# D5035-51.net
KiCad netlist of a schematic drawn in Altium Designer
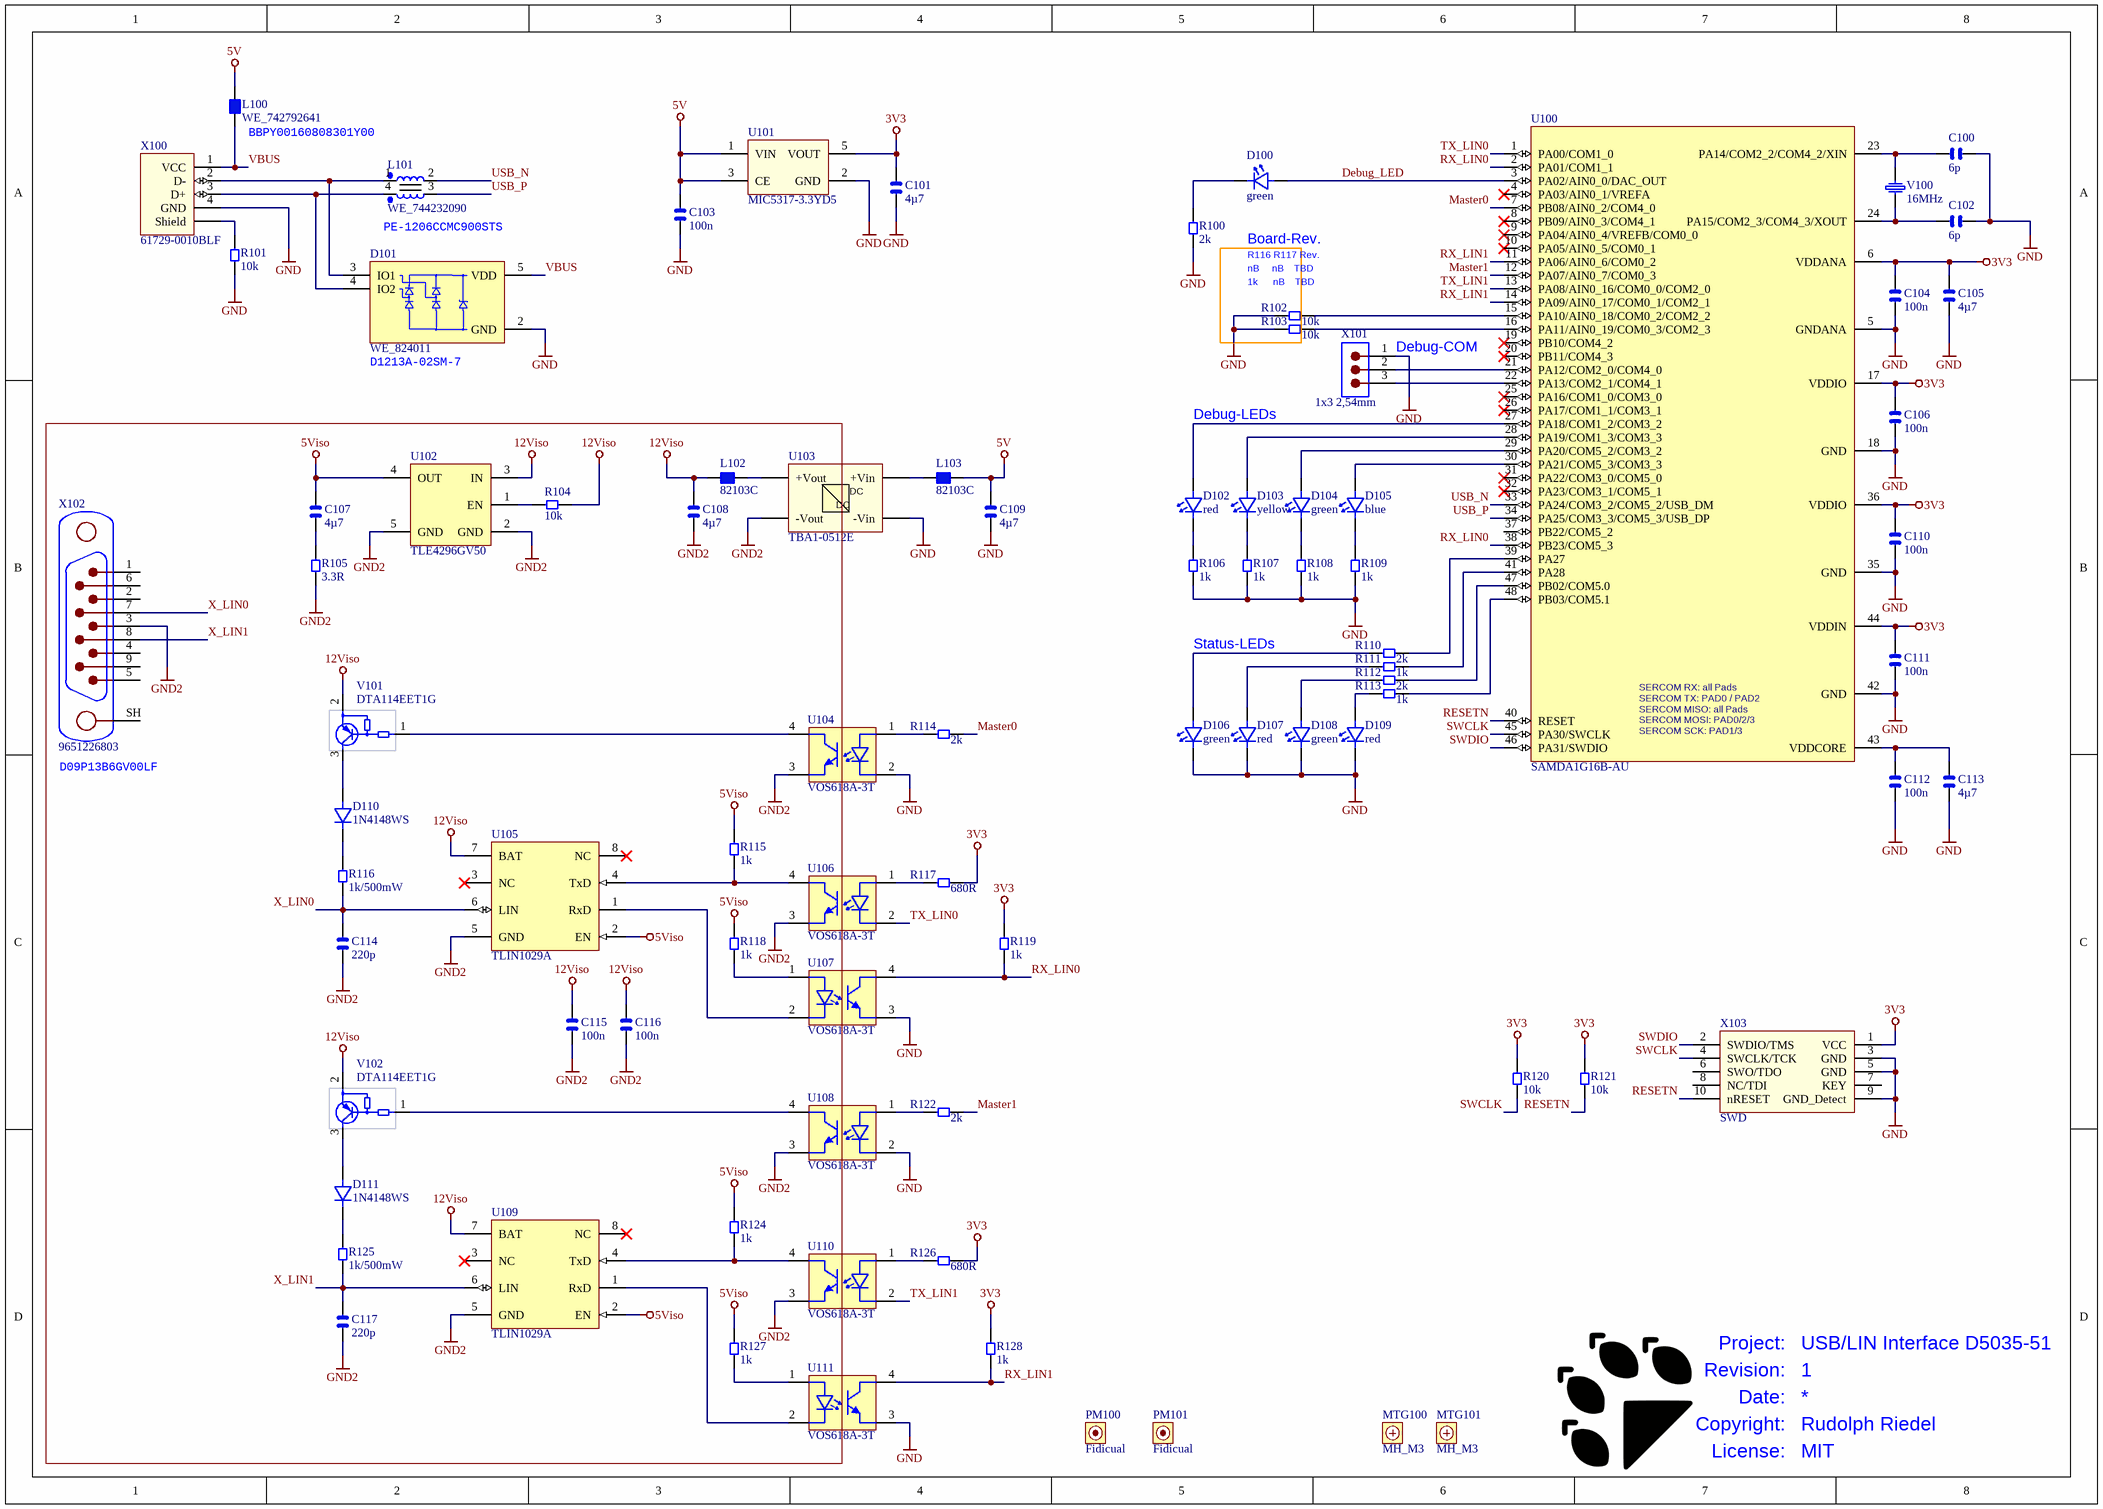
[diagram p0: D5035-51.SchDoc]

(export (version "E")
  (design (tool "Eeschema 10.0.6"))
  (components
    (comp (ref "C100")
      (value "6p")
      (footprint "CAPC1608X09L")
      (description "0603 Chip Capacitor")
      (fields (field (name "PART NUMBER") "CAPC_0603") (field (name "EDITOR") "rriedel"))
      (libsource (lib "HW-Labor_GF") (part "CAP_2_V2"))
    )
    (comp (ref "C101")
      (value "4µ7")
      (footprint "CAPC2012X14L")
      (description "0805 Chip Capacitor")
      (fields (field (name "PART NUMBER") "CAPC_0805") (field (name "EDITOR") "rriedel"))
      (libsource (lib "HW-Labor_GF") (part "CAP_2_V2"))
    )
    (comp (ref "C102")
      (value "6p")
      (footprint "CAPC1608X09L")
      (description "0603 Chip Capacitor")
      (fields (field (name "PART NUMBER") "CAPC_0603") (field (name "EDITOR") "rriedel"))
      (libsource (lib "HW-Labor_GF") (part "CAP_2_V2"))
    )
    (comp (ref "C103")
      (value "100n")
      (footprint "CAPC1608X09L")
      (description "0603 Chip Capacitor")
      (fields (field (name "PART NUMBER") "CAPC_0603") (field (name "EDITOR") "rriedel"))
      (libsource (lib "HW-Labor_GF") (part "CAP_2_V2"))
    )
    (comp (ref "C104")
      (value "100n")
      (footprint "CAPC1608X09L")
      (description "0603 Chip Capacitor")
      (fields (field (name "PART NUMBER") "CAPC_0603") (field (name "EDITOR") "rriedel"))
      (libsource (lib "HW-Labor_GF") (part "CAP_2_V2"))
    )
    (comp (ref "C105")
      (value "4µ7")
      (footprint "CAPC2012X14L")
      (description "0805 Chip Capacitor")
      (fields (field (name "PART NUMBER") "CAPC_0805") (field (name "EDITOR") "rriedel"))
      (libsource (lib "HW-Labor_GF") (part "CAP_2_V2"))
    )
    (comp (ref "C106")
      (value "100n")
      (footprint "CAPC1608X09L")
      (description "0603 Chip Capacitor")
      (fields (field (name "PART NUMBER") "CAPC_0603") (field (name "EDITOR") "rriedel"))
      (libsource (lib "HW-Labor_GF") (part "CAP_2_V2"))
    )
    (comp (ref "C107")
      (value "4µ7")
      (footprint "CAPC2012X14L")
      (description "0805 Chip Capacitor")
      (fields (field (name "PART NUMBER") "CAPC_0805") (field (name "EDITOR") "rriedel"))
      (libsource (lib "HW-Labor_GF") (part "CAP_2_V2"))
    )
    (comp (ref "C108")
      (value "4µ7")
      (footprint "CAPC2012X14L")
      (description "0805 Chip Capacitor")
      (fields (field (name "PART NUMBER") "CAPC_0805") (field (name "EDITOR") "rriedel"))
      (libsource (lib "HW-Labor_GF") (part "CAP_2_V2"))
    )
    (comp (ref "C109")
      (value "4µ7")
      (footprint "CAPC2012X14L")
      (description "0805 Chip Capacitor")
      (fields (field (name "PART NUMBER") "CAPC_0805") (field (name "EDITOR") "rriedel"))
      (libsource (lib "HW-Labor_GF") (part "CAP_2_V2"))
    )
    (comp (ref "C110")
      (value "100n")
      (footprint "CAPC1608X09L")
      (description "0603 Chip Capacitor")
      (fields (field (name "PART NUMBER") "CAPC_0603") (field (name "EDITOR") "rriedel"))
      (libsource (lib "HW-Labor_GF") (part "CAP_2_V2"))
    )
    (comp (ref "C111")
      (value "100n")
      (footprint "CAPC1608X09L")
      (description "0603 Chip Capacitor")
      (fields (field (name "PART NUMBER") "CAPC_0603") (field (name "EDITOR") "rriedel"))
      (libsource (lib "HW-Labor_GF") (part "CAP_2_V2"))
    )
    (comp (ref "C112")
      (value "100n")
      (footprint "CAPC1608X09L")
      (description "0603 Chip Capacitor")
      (fields (field (name "PART NUMBER") "CAPC_0603") (field (name "EDITOR") "rriedel"))
      (libsource (lib "HW-Labor_GF") (part "CAP_2_V2"))
    )
    (comp (ref "C113")
      (value "4µ7")
      (footprint "CAPC2012X14L")
      (description "0805 Chip Capacitor")
      (fields (field (name "PART NUMBER") "CAPC_0805") (field (name "EDITOR") "rriedel"))
      (libsource (lib "HW-Labor_GF") (part "CAP_2_V2"))
    )
    (comp (ref "C114")
      (value "220p")
      (footprint "CAPC2012X14L")
      (description "0805 Chip Capacitor")
      (fields (field (name "PART NUMBER") "CAPC_0805") (field (name "EDITOR") "rriedel"))
      (libsource (lib "HW-Labor_GF") (part "CAP_2_V2"))
    )
    (comp (ref "C115")
      (value "100n")
      (footprint "CAPC1608X09L")
      (description "0603 Chip Capacitor")
      (fields (field (name "PART NUMBER") "CAPC_0603") (field (name "EDITOR") "rriedel"))
      (libsource (lib "HW-Labor_GF") (part "CAP_2_V2"))
    )
    (comp (ref "C116")
      (value "100n")
      (footprint "CAPC1608X09L")
      (description "0603 Chip Capacitor")
      (fields (field (name "PART NUMBER") "CAPC_0603") (field (name "EDITOR") "rriedel"))
      (libsource (lib "HW-Labor_GF") (part "CAP_2_V2"))
    )
    (comp (ref "C117")
      (value "220p")
      (footprint "CAPC2012X14L")
      (description "0805 Chip Capacitor")
      (fields (field (name "PART NUMBER") "CAPC_0805") (field (name "EDITOR") "rriedel"))
      (libsource (lib "HW-Labor_GF") (part "CAP_2_V2"))
    )
    (comp (ref "D100")
      (value "green")
      (footprint "DIOC1608X06N_LED")
      (description "LED, 0603")
      (fields (field (name "PART NUMBER") "LED_0603") (field (name "EDITOR") "rriedel"))
      (libsource (lib "HW-Labor_GF") (part "LED_generic"))
    )
    (comp (ref "D101")
      (value "WE_824011")
      (footprint "SOT95P280X110-5N")
      (description "TVS Diode Array WE-TVS")
      (fields
        (field (name "MANUFACTURER") "Wuerth")
        (field (name "DISTRIBUTOR_1_PART_NUMBER") "732-4465-1-ND")
        (field (name "EDITOR") "rriedel")
      )
      (libsource (lib "HW-Labor_GF") (part "WE-824011"))
    )
    (comp (ref "D102")
      (value "red")
      (footprint "DIOC1608X06N_LED")
      (description "LED, 0603")
      (fields (field (name "PART NUMBER") "LED_0603") (field (name "EDITOR") "rriedel"))
      (libsource (lib "HW-Labor_GF") (part "LED_generic"))
    )
    (comp (ref "D103")
      (value "yellow")
      (footprint "DIOC1608X06N_LED")
      (description "LED, 0603")
      (fields (field (name "PART NUMBER") "LED_0603") (field (name "EDITOR") "rriedel"))
      (libsource (lib "HW-Labor_GF") (part "LED_generic"))
    )
    (comp (ref "D104")
      (value "green")
      (footprint "DIOC1608X06N_LED")
      (description "LED, 0603")
      (fields (field (name "PART NUMBER") "LED_0603") (field (name "EDITOR") "rriedel"))
      (libsource (lib "HW-Labor_GF") (part "LED_generic"))
    )
    (comp (ref "D105")
      (value "blue")
      (footprint "DIOC1608X06N_LED")
      (description "LED, 0603")
      (fields (field (name "PART NUMBER") "LED_0603") (field (name "EDITOR") "rriedel"))
      (libsource (lib "HW-Labor_GF") (part "LED_generic"))
    )
    (comp (ref "D106")
      (value "green")
      (footprint "DIOC1608X06N_LED")
      (description "LED, 0603")
      (fields (field (name "PART NUMBER") "LED_0603") (field (name "EDITOR") "rriedel"))
      (libsource (lib "HW-Labor_GF") (part "LED_generic"))
    )
    (comp (ref "D107")
      (value "red")
      (footprint "DIOC1608X06N_LED")
      (description "LED, 0603")
      (fields (field (name "PART NUMBER") "LED_0603") (field (name "EDITOR") "rriedel"))
      (libsource (lib "HW-Labor_GF") (part "LED_generic"))
    )
    (comp (ref "D108")
      (value "green")
      (footprint "DIOC1608X06N_LED")
      (description "LED, 0603")
      (fields (field (name "PART NUMBER") "LED_0603") (field (name "EDITOR") "rriedel"))
      (libsource (lib "HW-Labor_GF") (part "LED_generic"))
    )
    (comp (ref "D109")
      (value "red")
      (footprint "DIOC1608X06N_LED")
      (description "LED, 0603")
      (fields (field (name "PART NUMBER") "LED_0603") (field (name "EDITOR") "rriedel"))
      (libsource (lib "HW-Labor_GF") (part "LED_generic"))
    )
    (comp (ref "D110")
      (value "1N4148WS")
      (footprint "SOD323")
      (description "Small Signal Diode IF 0.15A, VR 75V, SOD323F")
      (fields (field (name "DISTRIBUTOR_1_PART_NUMBER") "C2128") (field (name "EDITOR") "rriedel"))
      (libsource (lib "HW-Labor_GF") (part "Diode_A2_K1"))
    )
    (comp (ref "D111")
      (value "1N4148WS")
      (footprint "SOD323")
      (description "Small Signal Diode IF 0.15A, VR 75V, SOD323F")
      (fields (field (name "DISTRIBUTOR_1_PART_NUMBER") "C2128") (field (name "EDITOR") "rriedel"))
      (libsource (lib "HW-Labor_GF") (part "Diode_A2_K1"))
    )
    (comp (ref "L100")
      (value "WE_742792641")
      (footprint "INDC1608X06L")
      (description "SMT EMI suppression ferrite bead WE-CBF")
      (fields
        (field (name "MANUFACTURER") "Wuerth")
        (field (name "DISTRIBUTOR_1_PART_NUMBER") "732-1592-1-ND")
        (field (name "EDITOR") "rriedel")
      )
      (libsource (lib "HW-Labor_GF") (part "IND_2_V1"))
    )
    (comp (ref "L101")
      (value "WE_744232090")
      (footprint "WE_744232090")
      (description "SMD common mode noise suppressor WE-CNSW")
      (fields
        (field (name "MANUFACTURER") "Wuerth")
        (field (name "DISTRIBUTOR_1_PART_NUMBER") "732-1469-1-ND")
        (field (name "EDITOR") "rriedel")
      )
      (libsource (lib "HW-Labor_GF") (part "WE_744232090"))
    )
    (comp (ref "L102")
      (value "82103C")
      (footprint "Murata_8200C")
      (description "10µH, 0,5A, 400mR")
      (fields
        (field (name "MANUFACTURER") "Murata")
        (field (name "DISTRIBUTOR_1_PART_NUMBER") "811-2473-1-ND")
        (field (name "EDITOR") "rriedel")
      )
      (libsource (lib "HW-Labor_GF") (part "IND_2_V1"))
    )
    (comp (ref "L103")
      (value "82103C")
      (footprint "Murata_8200C")
      (description "10µH, 0,5A, 400mR")
      (fields
        (field (name "MANUFACTURER") "Murata")
        (field (name "DISTRIBUTOR_1_PART_NUMBER") "811-2473-1-ND")
        (field (name "EDITOR") "rriedel")
      )
      (libsource (lib "HW-Labor_GF") (part "IND_2_V1"))
    )
    (comp (ref "MTG100")
      (value "MH_M3")
      (footprint "HOLE_3_2MM")
      (description "Mounting-Hole for M3 screws")
      (fields (field (name "EDITOR") "rriedel"))
      (libsource (lib "HW-Labor_GF") (part "MTG_V1"))
    )
    (comp (ref "MTG101")
      (value "MH_M3")
      (footprint "HOLE_3_2MM")
      (description "Mounting-Hole for M3 screws")
      (fields (field (name "EDITOR") "rriedel"))
      (libsource (lib "HW-Labor_GF") (part "MTG_V1"))
    )
    (comp (ref "PM100")
      (value "Fidicual")
      (footprint "PM100")
      (fields (field (name "PART NUMBER") "PM100") (field (name "EDITOR") "rriedel"))
      (libsource (lib "HW-Labor_GF") (part "PM100"))
    )
    (comp (ref "PM101")
      (value "Fidicual")
      (footprint "PM100")
      (fields (field (name "PART NUMBER") "PM100") (field (name "EDITOR") "rriedel"))
      (libsource (lib "HW-Labor_GF") (part "PM100"))
    )
    (comp (ref "R100")
      (value "2k")
      (footprint "RESC1608X06L")
      (description "0603 Chip Resistor")
      (fields (field (name "PART NUMBER") "RESC_0603") (field (name "EDITOR") "rriedel"))
      (libsource (lib "HW-Labor_GF") (part "RES_2_V2"))
    )
    (comp (ref "R101")
      (value "10k")
      (footprint "RESC1608X06L")
      (description "0603 Chip Resistor")
      (fields (field (name "PART NUMBER") "RESC_0603") (field (name "EDITOR") "rriedel"))
      (libsource (lib "HW-Labor_GF") (part "RES_2_V2"))
    )
    (comp (ref "R102")
      (value "10k")
      (footprint "RESC1608X06L")
      (description "0603 Chip Resistor")
      (fields (field (name "PART NUMBER") "RESC_0603") (field (name "EDITOR") "rriedel"))
      (libsource (lib "HW-Labor_GF") (part "RES_2_V2"))
    )
    (comp (ref "R103")
      (value "10k")
      (footprint "RESC1608X06L")
      (description "0603 Chip Resistor")
      (fields (field (name "PART NUMBER") "RESC_0603") (field (name "EDITOR") "rriedel"))
      (libsource (lib "HW-Labor_GF") (part "RES_2_V2"))
    )
    (comp (ref "R104")
      (value "10k")
      (footprint "RESC1608X06L")
      (description "0603 Chip Resistor")
      (fields (field (name "PART NUMBER") "RESC_0603") (field (name "EDITOR") "rriedel"))
      (libsource (lib "HW-Labor_GF") (part "RES_2_V2"))
    )
    (comp (ref "R105")
      (value "3.3R")
      (footprint "RESC1608X06L")
      (description "0603 Chip Resistor")
      (fields (field (name "PART NUMBER") "RESC_0603") (field (name "EDITOR") "rriedel"))
      (libsource (lib "HW-Labor_GF") (part "RES_2_V2"))
    )
    (comp (ref "R106")
      (value "1k")
      (footprint "RESC1608X06L")
      (description "0603 Chip Resistor")
      (fields (field (name "PART NUMBER") "RESC_0603") (field (name "EDITOR") "rriedel"))
      (libsource (lib "HW-Labor_GF") (part "RES_2_V2"))
    )
    (comp (ref "R107")
      (value "1k")
      (footprint "RESC1608X06L")
      (description "0603 Chip Resistor")
      (fields (field (name "PART NUMBER") "RESC_0603") (field (name "EDITOR") "rriedel"))
      (libsource (lib "HW-Labor_GF") (part "RES_2_V2"))
    )
    (comp (ref "R108")
      (value "1k")
      (footprint "RESC1608X06L")
      (description "0603 Chip Resistor")
      (fields (field (name "PART NUMBER") "RESC_0603") (field (name "EDITOR") "rriedel"))
      (libsource (lib "HW-Labor_GF") (part "RES_2_V2"))
    )
    (comp (ref "R109")
      (value "1k")
      (footprint "RESC1608X06L")
      (description "0603 Chip Resistor")
      (fields (field (name "PART NUMBER") "RESC_0603") (field (name "EDITOR") "rriedel"))
      (libsource (lib "HW-Labor_GF") (part "RES_2_V2"))
    )
    (comp (ref "R110")
      (value "2k")
      (footprint "RESC1608X06L")
      (description "0603 Chip Resistor")
      (fields (field (name "PART NUMBER") "RESC_0603") (field (name "EDITOR") "rriedel"))
      (libsource (lib "HW-Labor_GF") (part "RES_2_V2"))
    )
    (comp (ref "R111")
      (value "1k")
      (footprint "RESC1608X06L")
      (description "0603 Chip Resistor")
      (fields (field (name "PART NUMBER") "RESC_0603") (field (name "EDITOR") "rriedel"))
      (libsource (lib "HW-Labor_GF") (part "RES_2_V2"))
    )
    (comp (ref "R112")
      (value "2k")
      (footprint "RESC1608X06L")
      (description "0603 Chip Resistor")
      (fields (field (name "PART NUMBER") "RESC_0603") (field (name "EDITOR") "rriedel"))
      (libsource (lib "HW-Labor_GF") (part "RES_2_V2"))
    )
    (comp (ref "R113")
      (value "1k")
      (footprint "RESC1608X06L")
      (description "0603 Chip Resistor")
      (fields (field (name "PART NUMBER") "RESC_0603") (field (name "EDITOR") "rriedel"))
      (libsource (lib "HW-Labor_GF") (part "RES_2_V2"))
    )
    (comp (ref "R114")
      (value "2k")
      (footprint "RESC1608X06L")
      (description "0603 Chip Resistor")
      (fields (field (name "PART NUMBER") "RESC_0603") (field (name "EDITOR") "rriedel"))
      (libsource (lib "HW-Labor_GF") (part "RES_2_V2"))
    )
    (comp (ref "R115")
      (value "1k")
      (footprint "RESC1608X06L")
      (description "0603 Chip Resistor")
      (fields (field (name "PART NUMBER") "RESC_0603") (field (name "EDITOR") "rriedel"))
      (libsource (lib "HW-Labor_GF") (part "RES_2_V2"))
    )
    (comp (ref "R116")
      (value "1k/500mW")
      (footprint "RESC2012X06L")
      (description "0805 Chip Resistor")
      (fields (field (name "PART NUMBER") "RESC_0805") (field (name "EDITOR") "rriedel"))
      (libsource (lib "HW-Labor_GF") (part "RES_2_V2"))
    )
    (comp (ref "R117")
      (value "680R")
      (footprint "RESC1608X06L")
      (description "0603 Chip Resistor")
      (fields (field (name "PART NUMBER") "RESC_0603") (field (name "EDITOR") "rriedel"))
      (libsource (lib "HW-Labor_GF") (part "RES_2_V2"))
    )
    (comp (ref "R118")
      (value "1k")
      (footprint "RESC1608X06L")
      (description "0603 Chip Resistor")
      (fields (field (name "PART NUMBER") "RESC_0603") (field (name "EDITOR") "rriedel"))
      (libsource (lib "HW-Labor_GF") (part "RES_2_V2"))
    )
    (comp (ref "R119")
      (value "1k")
      (footprint "RESC1608X06L")
      (description "0603 Chip Resistor")
      (fields (field (name "PART NUMBER") "RESC_0603") (field (name "EDITOR") "rriedel"))
      (libsource (lib "HW-Labor_GF") (part "RES_2_V2"))
    )
    (comp (ref "R120")
      (value "10k")
      (footprint "RESC1608X06L")
      (description "0603 Chip Resistor")
      (fields (field (name "PART NUMBER") "RESC_0603") (field (name "EDITOR") "rriedel"))
      (libsource (lib "HW-Labor_GF") (part "RES_2_V2"))
    )
    (comp (ref "R121")
      (value "10k")
      (footprint "RESC1608X06L")
      (description "0603 Chip Resistor")
      (fields (field (name "PART NUMBER") "RESC_0603") (field (name "EDITOR") "rriedel"))
      (libsource (lib "HW-Labor_GF") (part "RES_2_V2"))
    )
    (comp (ref "R122")
      (value "2k")
      (footprint "RESC1608X06L")
      (description "0603 Chip Resistor")
      (fields (field (name "PART NUMBER") "RESC_0603") (field (name "EDITOR") "rriedel"))
      (libsource (lib "HW-Labor_GF") (part "RES_2_V2"))
    )
    (comp (ref "R124")
      (value "1k")
      (footprint "RESC1608X06L")
      (description "0603 Chip Resistor")
      (fields (field (name "PART NUMBER") "RESC_0603") (field (name "EDITOR") "rriedel"))
      (libsource (lib "HW-Labor_GF") (part "RES_2_V2"))
    )
    (comp (ref "R125")
      (value "1k/500mW")
      (footprint "RESC2012X06L")
      (description "0805 Chip Resistor")
      (fields (field (name "PART NUMBER") "RESC_0805") (field (name "EDITOR") "rriedel"))
      (libsource (lib "HW-Labor_GF") (part "RES_2_V2"))
    )
    (comp (ref "R126")
      (value "680R")
      (footprint "RESC1608X06L")
      (description "0603 Chip Resistor")
      (fields (field (name "PART NUMBER") "RESC_0603") (field (name "EDITOR") "rriedel"))
      (libsource (lib "HW-Labor_GF") (part "RES_2_V2"))
    )
    (comp (ref "R127")
      (value "1k")
      (footprint "RESC1608X06L")
      (description "0603 Chip Resistor")
      (fields (field (name "PART NUMBER") "RESC_0603") (field (name "EDITOR") "rriedel"))
      (libsource (lib "HW-Labor_GF") (part "RES_2_V2"))
    )
    (comp (ref "R128")
      (value "1k")
      (footprint "RESC1608X06L")
      (description "0603 Chip Resistor")
      (fields (field (name "PART NUMBER") "RESC_0603") (field (name "EDITOR") "rriedel"))
      (libsource (lib "HW-Labor_GF") (part "RES_2_V2"))
    )
    (comp (ref "U100")
      (value "SAMDA1G16B-AU")
      (footprint "TQFP50P900X900X120-48N")
      (description "32-bit Microcontroller, 48MHz Cortex M0, 64k FLASH,  USB, -40…85°C")
      (fields
        (field (name "MANUFACTURER") "Microchip")
        (field (name "DISTRIBUTOR_1_PART_NUMBER") "556-ATSAMDA1G16B-ABT")
        (field (name "EDITOR") "rriedel")
      )
      (libsource (lib "HW-Labor_GF") (part "ATSAMDA1G1xB"))
    )
    (comp (ref "U101")
      (value "MIC5317-3.3YD5")
      (footprint "SOT95P280X110-5N")
      (description "100 mA LDO,  Vout= 3,3V, -40°C..125°C")
      (fields
        (field (name "PART NUMBER") "MIC5233-3.3")
        (field (name "MANUFACTURER") "Microchip")
        (field (name "EDITOR") "rriedel")
      )
      (libsource (lib "HW-Labor_GF") (part "LDO_SOT23-5"))
    )
    (comp (ref "U102")
      (value "TLE4296GV50")
      (footprint "INF-PG-SCT595V")
      (description "30 mA LDO, Vout = 5,0V, 4%")
      (fields (field (name "MANUFACTURER") "Infineon") (field (name "EDITOR") "rriedel"))
      (libsource (lib "HW-Labor_GF") (part "TLE4295GVxx"))
    )
    (comp (ref "U103")
      (value "TBA1-0512E")
      (footprint "MER1SxxxxC")
      (description "Isolated 1W Single Output DC-DC Converters 5V/12V 84mA")
      (fields
        (field (name "PART NUMBER") "MER1S0505SC")
        (field (name "MANUFACTURER") "Murata")
        (field (name "EDITOR") "rriedel")
      )
      (libsource (lib "HW-Labor_GF") (part "MER1SxxxxC"))
    )
    (comp (ref "U104")
      (value "VOS618A-3T")
      (footprint "SSOP-4")
      (description "Optocoupler, Phototransistor Output, Low Input Current, SSOP-4")
      (fields
        (field (name "MANUFACTURER") "Vishay")
        (field (name "DISTRIBUTOR_1_PART_NUMBER") "VOS618A-3TCT-ND‎")
        (field (name "EDITOR") "rriedel")
      )
      (libsource (lib "HW-Labor_GF") (part "VOS618A"))
    )
    (comp (ref "U105")
      (value "TLIN1029A")
      (footprint "SOIC127P600X175-8N")
      (description "LIN transceiver")
      (fields
        (field (name "MANUFACTURER") "TI")
        (field (name "DISTRIBUTOR_1_PART_NUMBER") "595-TLIN1029ADRQ1")
        (field (name "EDITOR") "rriedel")
      )
      (libsource (lib "HW-Labor_GF") (part "TLIN1029A"))
    )
    (comp (ref "U106")
      (value "VOS618A-3T")
      (footprint "SSOP-4")
      (description "Optocoupler, Phototransistor Output, Low Input Current, SSOP-4")
      (fields
        (field (name "MANUFACTURER") "Vishay")
        (field (name "DISTRIBUTOR_1_PART_NUMBER") "VOS618A-3TCT-ND‎")
        (field (name "EDITOR") "rriedel")
      )
      (libsource (lib "HW-Labor_GF") (part "VOS618A"))
    )
    (comp (ref "U107")
      (value "VOS618A-3T")
      (footprint "SSOP-4")
      (description "Optocoupler, Phototransistor Output, Low Input Current, SSOP-4")
      (fields
        (field (name "MANUFACTURER") "Vishay")
        (field (name "DISTRIBUTOR_1_PART_NUMBER") "VOS618A-3TCT-ND‎")
        (field (name "EDITOR") "rriedel")
      )
      (libsource (lib "") (part "VOS618A_1"))
    )
    (comp (ref "U108")
      (value "VOS618A-3T")
      (footprint "SSOP-4")
      (description "Optocoupler, Phototransistor Output, Low Input Current, SSOP-4")
      (fields
        (field (name "MANUFACTURER") "Vishay")
        (field (name "DISTRIBUTOR_1_PART_NUMBER") "VOS618A-3TCT-ND‎")
        (field (name "EDITOR") "rriedel")
      )
      (libsource (lib "HW-Labor_GF") (part "VOS618A"))
    )
    (comp (ref "U109")
      (value "TLIN1029A")
      (footprint "SOIC127P600X175-8N")
      (description "LIN transceiver")
      (fields
        (field (name "MANUFACTURER") "TI")
        (field (name "DISTRIBUTOR_1_PART_NUMBER") "595-TLIN1029ADRQ1")
        (field (name "EDITOR") "rriedel")
      )
      (libsource (lib "HW-Labor_GF") (part "TLIN1029A"))
    )
    (comp (ref "U110")
      (value "VOS618A-3T")
      (footprint "SSOP-4")
      (description "Optocoupler, Phototransistor Output, Low Input Current, SSOP-4")
      (fields
        (field (name "MANUFACTURER") "Vishay")
        (field (name "DISTRIBUTOR_1_PART_NUMBER") "VOS618A-3TCT-ND‎")
        (field (name "EDITOR") "rriedel")
      )
      (libsource (lib "HW-Labor_GF") (part "VOS618A"))
    )
    (comp (ref "U111")
      (value "VOS618A-3T")
      (footprint "SSOP-4")
      (description "Optocoupler, Phototransistor Output, Low Input Current, SSOP-4")
      (fields
        (field (name "MANUFACTURER") "Vishay")
        (field (name "DISTRIBUTOR_1_PART_NUMBER") "VOS618A-3TCT-ND‎")
        (field (name "EDITOR") "rriedel")
      )
      (libsource (lib "") (part "VOS618A_1"))
    )
    (comp (ref "V100")
      (value "16MHz")
      (footprint "NX3225Gx")
      (description "16.000MHz Crystal SMD, 3.2x2.5mm, 8pF, 50ppm,  -40..+150°C")
      (fields
        (field (name "PART NUMBER") "NX3225GB-16.000000MHZ")
        (field (name "MANUFACTURER") "NDK")
        (field (name "EDITOR") "rriedel")
      )
      (libsource (lib "HW-Labor_GF") (part "XTAL_2_V1"))
    )
    (comp (ref "V101")
      (value "DTA114EET1G")
      (footprint "SOT50P162X60-3N")
      (description "PNP Transistor with Resistors (10kΩ, 10kΩ)  VCE= 50V, IC=100mA, SOT23, AEC Q101")
      (fields (field (name "EDITOR") "rriedel"))
      (libsource (lib "HW-Labor_GF") (part "PNP_Digital"))
    )
    (comp (ref "V102")
      (value "DTA114EET1G")
      (footprint "SOT50P162X60-3N")
      (description "PNP Transistor with Resistors (10kΩ, 10kΩ)  VCE= 50V, IC=100mA, SOT23, AEC Q101")
      (fields (field (name "EDITOR") "rriedel"))
      (libsource (lib "HW-Labor_GF") (part "PNP_Digital"))
    )
    (comp (ref "X100")
      (value "61729-0010BLF")
      (footprint "61729-xxxxxLF")
      (description "USB-B socket, THT")
      (fields
        (field (name "MANUFACTURER") "Amphenol")
        (field (name "DISTRIBUTOR_1_PART_NUMBER") "609-1039-ND")
        (field (name "EDITOR") "rriedel")
      )
      (libsource (lib "HW-Labor_GF") (part "USB"))
    )
    (comp (ref "X101")
      (value "1x3 2,54mm")
      (footprint "PINH_1x03_2_54mm")
      (description "Pin-Header 2,54 mm 3pins")
      (fields (field (name "PART NUMBER") "PINH_1x3_2_54") (field (name "EDITOR") "rriedel"))
      (libsource (lib "HW-Labor_GF") (part "CONM_1x3_V2"))
    )
    (comp (ref "X102")
      (value "9651226803")
      (footprint "09651226803")
      (description "D-Sub, 9 pin, male, right angle")
      (fields
        (field (name "MANUFACTURER") "Harting")
        (field (name "DISTRIBUTOR_1_PART_NUMBER") "2752007")
        (field (name "EDITOR") "rriedel")
      )
      (libsource (lib "HW-Labor_GF") (part "D_Sub_9_Male"))
    )
    (comp (ref "X103")
      (value "SWD")
      (footprint "FTSH-105-01-L-DV-K")
      (description "ARM Debug-Header 2x5 1,27 mm")
      (fields (field (name "EDITOR") "rriedel"))
      (libsource (lib "HW-Labor_GF") (part "SWD"))
    )
  )
  (nets
    (net (code "1") (name "/Debug_LED") (class "Default")
      (node (ref "D100") (pin "2") (pinfunction "2_2") (pintype "passive"))
      (node (ref "U100") (pin "3") (pinfunction "PA02/AIN0_0/DAC_OUT_3") (pintype "bidirectional"))
    )
    (net (code "2") (name "/Master0") (class "Default")
      (node (ref "R114") (pin "1") (pinfunction "1_1") (pintype "passive"))
      (node (ref "U100") (pin "7") (pinfunction "PB08/AIN0_2/COM4_0_7") (pintype "bidirectional"))
    )
    (net (code "3") (name "/Master1") (class "Default")
      (node (ref "R122") (pin "1") (pinfunction "1_1") (pintype "passive"))
      (node (ref "U100") (pin "12") (pinfunction "PA07/AIN0_7/COM0_3_12") (pintype "bidirectional"))
    )
    (net (code "4") (name "/RESETN") (class "Default")
      (node (ref "R121") (pin "2") (pinfunction "2_2") (pintype "passive"))
      (node (ref "U100") (pin "40") (pinfunction "RESET_40") (pintype "bidirectional"))
      (node (ref "X103") (pin "10") (pinfunction "nRESET_10") (pintype "passive"))
    )
    (net (code "5") (name "/RX_LIN0") (class "Default")
      (node (ref "R119") (pin "2") (pinfunction "2_2") (pintype "passive"))
      (node (ref "U100") (pin "2") (pinfunction "PA01/COM1_1_2") (pintype "bidirectional"))
      (node (ref "U100") (pin "38") (pinfunction "PB23/COM5_3_38") (pintype "bidirectional"))
      (node (ref "U107") (pin "4") (pinfunction "C_4") (pintype "passive"))
    )
    (net (code "6") (name "/RX_LIN1") (class "Default")
      (node (ref "R128") (pin "1") (pinfunction "1_1") (pintype "passive"))
      (node (ref "U100") (pin "11") (pinfunction "PA06/AIN0_6/COM0_2_11") (pintype "bidirectional"))
      (node (ref "U100") (pin "14") (pinfunction "PA09/AIN0_17/COM0_1/COM2_1_14") (pintype "bidirectional"))
      (node (ref "U111") (pin "4") (pinfunction "C_4") (pintype "passive"))
    )
    (net (code "7") (name "/SWCLK") (class "Default")
      (node (ref "R120") (pin "2") (pinfunction "2_2") (pintype "passive"))
      (node (ref "U100") (pin "45") (pinfunction "PA30/SWCLK_45") (pintype "bidirectional"))
      (node (ref "X103") (pin "4") (pinfunction "SWCLK/TCK_4") (pintype "passive"))
    )
    (net (code "8") (name "/SWDIO") (class "Default")
      (node (ref "U100") (pin "46") (pinfunction "PA31/SWDIO_46") (pintype "bidirectional"))
      (node (ref "X103") (pin "2") (pinfunction "SWDIO/TMS_2") (pintype "passive"))
    )
    (net (code "9") (name "/TX_LIN0") (class "Default")
      (node (ref "U100") (pin "1") (pinfunction "PA00/COM1_0_1") (pintype "bidirectional"))
      (node (ref "U106") (pin "2") (pinfunction "C_2") (pintype "passive"))
    )
    (net (code "10") (name "/TX_LIN1") (class "Default")
      (node (ref "U100") (pin "13") (pinfunction "PA08/AIN0_16/COM0_0/COM2_0_13") (pintype "bidirectional"))
      (node (ref "U110") (pin "2") (pinfunction "C_2") (pintype "passive"))
    )
    (net (code "11") (name "/USB_N") (class "Default")
      (node (ref "L101") (pin "2") (pinfunction "2_2") (pintype "passive"))
      (node (ref "U100") (pin "33") (pinfunction "PA24/COM3_2/COM5_2/USB_DM_33") (pintype "bidirectional"))
    )
    (net (code "12") (name "/USB_P") (class "Default")
      (node (ref "L101") (pin "3") (pinfunction "3_3") (pintype "passive"))
      (node (ref "U100") (pin "34") (pinfunction "PA25/COM3_3/COM5_3/USB_DP_34") (pintype "bidirectional"))
    )
    (net (code "13") (name "/VBUS") (class "Default")
      (node (ref "D101") (pin "5") (pinfunction "VDD_5") (pintype "passive"))
      (node (ref "L100") (pin "1") (pinfunction "1_1") (pintype "passive"))
      (node (ref "X100") (pin "1") (pinfunction "VCC_1") (pintype "power_in"))
    )
    (net (code "14") (name "/X_LIN0") (class "Default")
      (node (ref "C114") (pin "2") (pinfunction "2_2") (pintype "passive"))
      (node (ref "R116") (pin "1") (pinfunction "1_1") (pintype "passive"))
      (node (ref "U105") (pin "6") (pinfunction "LIN_6") (pintype "bidirectional"))
      (node (ref "X102") (pin "7") (pinfunction "7_7") (pintype "passive"))
    )
    (net (code "15") (name "/X_LIN1") (class "Default")
      (node (ref "C117") (pin "2") (pinfunction "2_2") (pintype "passive"))
      (node (ref "R125") (pin "1") (pinfunction "1_1") (pintype "passive"))
      (node (ref "U109") (pin "6") (pinfunction "LIN_6") (pintype "bidirectional"))
      (node (ref "X102") (pin "8") (pinfunction "8_8") (pintype "passive"))
    )
    (net (code "16") (name "3V3") (class "Default")
      (node (ref "C101") (pin "2") (pinfunction "2_2") (pintype "passive"))
      (node (ref "C104") (pin "2") (pinfunction "2_2") (pintype "passive"))
      (node (ref "C105") (pin "2") (pinfunction "2_2") (pintype "passive"))
      (node (ref "C106") (pin "2") (pinfunction "2_2") (pintype "passive"))
      (node (ref "C110") (pin "2") (pinfunction "2_2") (pintype "passive"))
      (node (ref "C111") (pin "2") (pinfunction "2_2") (pintype "passive"))
      (node (ref "R117") (pin "1") (pinfunction "1_1") (pintype "passive"))
      (node (ref "R119") (pin "1") (pinfunction "1_1") (pintype "passive"))
      (node (ref "R120") (pin "1") (pinfunction "1_1") (pintype "passive"))
      (node (ref "R121") (pin "1") (pinfunction "1_1") (pintype "passive"))
      (node (ref "R126") (pin "1") (pinfunction "1_1") (pintype "passive"))
      (node (ref "R128") (pin "2") (pinfunction "2_2") (pintype "passive"))
      (node (ref "U100") (pin "17") (pinfunction "VDDIO_17") (pintype "power_in"))
      (node (ref "U100") (pin "36") (pinfunction "VDDIO_36") (pintype "power_in"))
      (node (ref "U100") (pin "44") (pinfunction "VDDIN_44") (pintype "power_in"))
      (node (ref "U100") (pin "6") (pinfunction "VDDANA_6") (pintype "power_in"))
      (node (ref "U101") (pin "5") (pinfunction "VOUT_5") (pintype "passive"))
      (node (ref "X103") (pin "1") (pinfunction "VCC_1") (pintype "power_in"))
    )
    (net (code "17") (name "5V") (class "Default")
      (node (ref "C103") (pin "2") (pinfunction "2_2") (pintype "passive"))
      (node (ref "C109") (pin "2") (pinfunction "2_2") (pintype "passive"))
      (node (ref "L100") (pin "2") (pinfunction "2_2") (pintype "passive"))
      (node (ref "L103") (pin "1") (pinfunction "1_1") (pintype "passive"))
      (node (ref "U101") (pin "1") (pinfunction "VIN_1") (pintype "passive"))
      (node (ref "U101") (pin "3") (pinfunction "CE_3") (pintype "passive"))
    )
    (net (code "18") (name "5Viso") (class "Default")
      (node (ref "C107") (pin "2") (pinfunction "2_2") (pintype "passive"))
      (node (ref "R115") (pin "1") (pinfunction "1_1") (pintype "passive"))
      (node (ref "R118") (pin "1") (pinfunction "1_1") (pintype "passive"))
      (node (ref "R124") (pin "2") (pinfunction "2_2") (pintype "passive"))
      (node (ref "R127") (pin "2") (pinfunction "2_2") (pintype "passive"))
      (node (ref "U102") (pin "4") (pinfunction "OUT_4") (pintype "passive"))
      (node (ref "U105") (pin "2") (pinfunction "EN_2") (pintype "input"))
      (node (ref "U109") (pin "2") (pinfunction "EN_2") (pintype "input"))
    )
    (net (code "19") (name "12Viso") (class "Default")
      (node (ref "C108") (pin "2") (pinfunction "2_2") (pintype "passive"))
      (node (ref "C115") (pin "2") (pinfunction "2_2") (pintype "passive"))
      (node (ref "C116") (pin "2") (pinfunction "2_2") (pintype "passive"))
      (node (ref "L102") (pin "2") (pinfunction "2_2") (pintype "passive"))
      (node (ref "R104") (pin "2") (pinfunction "2_2") (pintype "passive"))
      (node (ref "U102") (pin "3") (pinfunction "IN_3") (pintype "passive"))
      (node (ref "U105") (pin "7") (pinfunction "BAT_7") (pintype "power_in"))
      (node (ref "U109") (pin "7") (pinfunction "BAT_7") (pintype "power_in"))
      (node (ref "V101") (pin "2") (pinfunction "2_2") (pintype "passive"))
      (node (ref "V102") (pin "2") (pinfunction "2_2") (pintype "passive"))
    )
    (net (code "20") (name "GND") (class "Default")
      (node (ref "C100") (pin "2") (pinfunction "2_2") (pintype "passive"))
      (node (ref "C101") (pin "1") (pinfunction "1_1") (pintype "passive"))
      (node (ref "C102") (pin "2") (pinfunction "2_2") (pintype "passive"))
      (node (ref "C103") (pin "1") (pinfunction "1_1") (pintype "passive"))
      (node (ref "C104") (pin "1") (pinfunction "1_1") (pintype "passive"))
      (node (ref "C105") (pin "1") (pinfunction "1_1") (pintype "passive"))
      (node (ref "C106") (pin "1") (pinfunction "1_1") (pintype "passive"))
      (node (ref "C109") (pin "1") (pinfunction "1_1") (pintype "passive"))
      (node (ref "C110") (pin "1") (pinfunction "1_1") (pintype "passive"))
      (node (ref "C111") (pin "1") (pinfunction "1_1") (pintype "passive"))
      (node (ref "C112") (pin "1") (pinfunction "1_1") (pintype "passive"))
      (node (ref "C113") (pin "1") (pinfunction "1_1") (pintype "passive"))
      (node (ref "D101") (pin "2") (pinfunction "GND_2") (pintype "passive"))
      (node (ref "D106") (pin "1") (pinfunction "1_1") (pintype "passive"))
      (node (ref "D107") (pin "1") (pinfunction "1_1") (pintype "passive"))
      (node (ref "D108") (pin "1") (pinfunction "1_1") (pintype "passive"))
      (node (ref "D109") (pin "1") (pinfunction "1_1") (pintype "passive"))
      (node (ref "R100") (pin "1") (pinfunction "1_1") (pintype "passive"))
      (node (ref "R101") (pin "1") (pinfunction "1_1") (pintype "passive"))
      (node (ref "R102") (pin "2") (pinfunction "2_2") (pintype "passive"))
      (node (ref "R103") (pin "2") (pinfunction "2_2") (pintype "passive"))
      (node (ref "R106") (pin "1") (pinfunction "1_1") (pintype "passive"))
      (node (ref "R107") (pin "1") (pinfunction "1_1") (pintype "passive"))
      (node (ref "R108") (pin "1") (pinfunction "1_1") (pintype "passive"))
      (node (ref "R109") (pin "1") (pinfunction "1_1") (pintype "passive"))
      (node (ref "U100") (pin "18") (pinfunction "GND_18") (pintype "power_in"))
      (node (ref "U100") (pin "35") (pinfunction "GND_35") (pintype "power_in"))
      (node (ref "U100") (pin "42") (pinfunction "GND_42") (pintype "power_in"))
      (node (ref "U100") (pin "5") (pinfunction "GNDANA_5") (pintype "power_in"))
      (node (ref "U101") (pin "2") (pinfunction "GND_2") (pintype "passive"))
      (node (ref "U103") (pin "2") (pinfunction "-Vin_2") (pintype "power_in"))
      (node (ref "U104") (pin "2") (pinfunction "C_2") (pintype "passive"))
      (node (ref "U107") (pin "3") (pinfunction "E_3") (pintype "passive"))
      (node (ref "U108") (pin "2") (pinfunction "C_2") (pintype "passive"))
      (node (ref "U111") (pin "3") (pinfunction "E_3") (pintype "passive"))
      (node (ref "X100") (pin "4") (pinfunction "GND_4") (pintype "power_in"))
      (node (ref "X101") (pin "1") (pinfunction "1_1") (pintype "passive"))
      (node (ref "X103") (pin "3") (pinfunction "GND_3") (pintype "power_in"))
      (node (ref "X103") (pin "5") (pinfunction "GND_5") (pintype "power_in"))
      (node (ref "X103") (pin "9") (pinfunction "GND_Detect_9") (pintype "power_in"))
    )
    (net (code "21") (name "GND2") (class "Default")
      (node (ref "C108") (pin "1") (pinfunction "1_1") (pintype "passive"))
      (node (ref "C114") (pin "1") (pinfunction "1_1") (pintype "passive"))
      (node (ref "C115") (pin "1") (pinfunction "1_1") (pintype "passive"))
      (node (ref "C116") (pin "1") (pinfunction "1_1") (pintype "passive"))
      (node (ref "C117") (pin "1") (pinfunction "1_1") (pintype "passive"))
      (node (ref "R105") (pin "2") (pinfunction "2_2") (pintype "passive"))
      (node (ref "U102") (pin "2") (pinfunction "GND_2") (pintype "passive"))
      (node (ref "U102") (pin "5") (pinfunction "GND_5") (pintype "passive"))
      (node (ref "U103") (pin "4") (pinfunction "-Vout_4") (pintype "power_in"))
      (node (ref "U104") (pin "3") (pinfunction "E_3") (pintype "passive"))
      (node (ref "U105") (pin "5") (pinfunction "GND_5") (pintype "power_in"))
      (node (ref "U106") (pin "3") (pinfunction "E_3") (pintype "passive"))
      (node (ref "U108") (pin "3") (pinfunction "E_3") (pintype "passive"))
      (node (ref "U109") (pin "5") (pinfunction "GND_5") (pintype "power_in"))
      (node (ref "U110") (pin "3") (pinfunction "E_3") (pintype "passive"))
      (node (ref "X102") (pin "3") (pinfunction "3_3") (pintype "passive"))
    )
    (net (code "22") (name "Net-(C107-Pad1)") (class "Default")
      (node (ref "C107") (pin "1") (pinfunction "1_1") (pintype "passive"))
      (node (ref "R105") (pin "1") (pinfunction "1_1") (pintype "passive"))
    )
    (net (code "23") (name "Net-(D100-Pad1)") (class "Default")
      (node (ref "D100") (pin "1") (pinfunction "1_1") (pintype "passive"))
      (node (ref "R100") (pin "2") (pinfunction "2_2") (pintype "passive"))
    )
    (net (code "24") (name "Net-(D101-IO1)") (class "Default")
      (node (ref "D101") (pin "3") (pinfunction "IO1_3") (pintype "passive"))
      (node (ref "L101") (pin "1") (pinfunction "1_1") (pintype "passive"))
      (node (ref "X100") (pin "2") (pinfunction "D-_2") (pintype "bidirectional"))
    )
    (net (code "25") (name "Net-(D101-IO2)") (class "Default")
      (node (ref "D101") (pin "4") (pinfunction "IO2_4") (pintype "passive"))
      (node (ref "L101") (pin "4") (pinfunction "4_4") (pintype "passive"))
      (node (ref "X100") (pin "3") (pinfunction "D+_3") (pintype "bidirectional"))
    )
    (net (code "26") (name "Net-(D102-Pad1)") (class "Default")
      (node (ref "D102") (pin "1") (pinfunction "1_1") (pintype "passive"))
      (node (ref "R106") (pin "2") (pinfunction "2_2") (pintype "passive"))
    )
    (net (code "27") (name "Net-(D103-Pad1)") (class "Default")
      (node (ref "D103") (pin "1") (pinfunction "1_1") (pintype "passive"))
      (node (ref "R107") (pin "2") (pinfunction "2_2") (pintype "passive"))
    )
    (net (code "28") (name "Net-(D104-Pad1)") (class "Default")
      (node (ref "D104") (pin "1") (pinfunction "1_1") (pintype "passive"))
      (node (ref "R108") (pin "2") (pinfunction "2_2") (pintype "passive"))
    )
    (net (code "29") (name "Net-(D105-Pad1)") (class "Default")
      (node (ref "D105") (pin "1") (pinfunction "1_1") (pintype "passive"))
      (node (ref "R109") (pin "2") (pinfunction "2_2") (pintype "passive"))
    )
    (net (code "30") (name "Net-(D106-Pad2)") (class "Default")
      (node (ref "D106") (pin "2") (pinfunction "2_2") (pintype "passive"))
      (node (ref "R110") (pin "1") (pinfunction "1_1") (pintype "passive"))
    )
    (net (code "31") (name "Net-(D107-Pad2)") (class "Default")
      (node (ref "D107") (pin "2") (pinfunction "2_2") (pintype "passive"))
      (node (ref "R111") (pin "1") (pinfunction "1_1") (pintype "passive"))
    )
    (net (code "32") (name "Net-(D108-Pad2)") (class "Default")
      (node (ref "D108") (pin "2") (pinfunction "2_2") (pintype "passive"))
      (node (ref "R112") (pin "1") (pinfunction "1_1") (pintype "passive"))
    )
    (net (code "33") (name "Net-(D109-Pad2)") (class "Default")
      (node (ref "D109") (pin "2") (pinfunction "2_2") (pintype "passive"))
      (node (ref "R113") (pin "1") (pinfunction "1_1") (pintype "passive"))
    )
    (net (code "34") (name "Net-(D110-Pad1)") (class "Default")
      (node (ref "D110") (pin "1") (pinfunction "1_1") (pintype "passive"))
      (node (ref "R116") (pin "2") (pinfunction "2_2") (pintype "passive"))
    )
    (net (code "35") (name "Net-(D110-Pad2)") (class "Default")
      (node (ref "D110") (pin "2") (pinfunction "2_2") (pintype "passive"))
      (node (ref "V101") (pin "3") (pinfunction "3_3") (pintype "passive"))
    )
    (net (code "36") (name "Net-(D111-Pad1)") (class "Default")
      (node (ref "D111") (pin "1") (pinfunction "1_1") (pintype "passive"))
      (node (ref "R125") (pin "2") (pinfunction "2_2") (pintype "passive"))
    )
    (net (code "37") (name "Net-(D111-Pad2)") (class "Default")
      (node (ref "D111") (pin "2") (pinfunction "2_2") (pintype "passive"))
      (node (ref "V102") (pin "3") (pinfunction "3_3") (pintype "passive"))
    )
    (net (code "38") (name "Net-(U100-PA10{slash}AIN0_18{slash}COM0_2{slash}COM2_2)") (class "Default")
      (node (ref "R102") (pin "1") (pinfunction "1_1") (pintype "passive"))
      (node (ref "U100") (pin "15") (pinfunction "PA10/AIN0_18/COM0_2/COM2_2_15") (pintype "bidirectional"))
    )
    (net (code "39") (name "Net-(U100-PA11{slash}AIN0_19{slash}COM0_3{slash}COM2_3)") (class "Default")
      (node (ref "R103") (pin "1") (pinfunction "1_1") (pintype "passive"))
      (node (ref "U100") (pin "16") (pinfunction "PA11/AIN0_19/COM0_3/COM2_3_16") (pintype "bidirectional"))
    )
    (net (code "40") (name "Net-(U100-PA12{slash}COM2_0{slash}COM4_0)") (class "Default")
      (node (ref "U100") (pin "21") (pinfunction "PA12/COM2_0/COM4_0_21") (pintype "bidirectional"))
      (node (ref "X101") (pin "2") (pinfunction "2_2") (pintype "passive"))
    )
    (net (code "41") (name "Net-(U100-PA13{slash}COM2_1{slash}COM4_1)") (class "Default")
      (node (ref "U100") (pin "22") (pinfunction "PA13/COM2_1/COM4_1_22") (pintype "bidirectional"))
      (node (ref "X101") (pin "3") (pinfunction "3_3") (pintype "passive"))
    )
    (net (code "42") (name "Net-(U100-PA14{slash}COM2_2{slash}COM4_2{slash}XIN)") (class "Default")
      (node (ref "C100") (pin "1") (pinfunction "1_1") (pintype "passive"))
      (node (ref "U100") (pin "23") (pinfunction "PA14/COM2_2/COM4_2/XIN_23") (pintype "passive"))
      (node (ref "V100") (pin "2") (pinfunction "2_2") (pintype "passive"))
    )
    (net (code "43") (name "Net-(U100-PA15{slash}COM2_3{slash}COM4_3{slash}XOUT)") (class "Default")
      (node (ref "C102") (pin "1") (pinfunction "1_1") (pintype "passive"))
      (node (ref "U100") (pin "24") (pinfunction "PA15/COM2_3/COM4_3/XOUT_24") (pintype "passive"))
      (node (ref "V100") (pin "1") (pinfunction "1_1") (pintype "passive"))
    )
    (net (code "44") (name "Net-(U100-PA18{slash}COM1_2{slash}COM3_2)") (class "Default")
      (node (ref "D102") (pin "2") (pinfunction "2_2") (pintype "passive"))
      (node (ref "U100") (pin "27") (pinfunction "PA18/COM1_2/COM3_2_27") (pintype "bidirectional"))
    )
    (net (code "45") (name "Net-(U100-PA19{slash}COM1_3{slash}COM3_3)") (class "Default")
      (node (ref "D103") (pin "2") (pinfunction "2_2") (pintype "passive"))
      (node (ref "U100") (pin "28") (pinfunction "PA19/COM1_3/COM3_3_28") (pintype "bidirectional"))
    )
    (net (code "46") (name "Net-(U100-PA20{slash}COM5_2{slash}COM3_2)") (class "Default")
      (node (ref "D104") (pin "2") (pinfunction "2_2") (pintype "passive"))
      (node (ref "U100") (pin "29") (pinfunction "PA20/COM5_2/COM3_2_29") (pintype "bidirectional"))
    )
    (net (code "47") (name "Net-(U100-PA21{slash}COM5_3{slash}COM3_3)") (class "Default")
      (node (ref "D105") (pin "2") (pinfunction "2_2") (pintype "passive"))
      (node (ref "U100") (pin "30") (pinfunction "PA21/COM5_3/COM3_3_30") (pintype "bidirectional"))
    )
    (net (code "48") (name "Net-(U100-PA27)") (class "Default")
      (node (ref "R110") (pin "2") (pinfunction "2_2") (pintype "passive"))
      (node (ref "U100") (pin "39") (pinfunction "PA27_39") (pintype "bidirectional"))
    )
    (net (code "49") (name "Net-(U100-PA28)") (class "Default")
      (node (ref "R111") (pin "2") (pinfunction "2_2") (pintype "passive"))
      (node (ref "U100") (pin "41") (pinfunction "PA28_41") (pintype "bidirectional"))
    )
    (net (code "50") (name "Net-(U100-PB02{slash}COM5.0)") (class "Default")
      (node (ref "R112") (pin "2") (pinfunction "2_2") (pintype "passive"))
      (node (ref "U100") (pin "47") (pinfunction "PB02/COM5.0_47") (pintype "bidirectional"))
    )
    (net (code "51") (name "Net-(U100-PB03{slash}COM5.1)") (class "Default")
      (node (ref "R113") (pin "2") (pinfunction "2_2") (pintype "passive"))
      (node (ref "U100") (pin "48") (pinfunction "PB03/COM5.1_48") (pintype "bidirectional"))
    )
    (net (code "52") (name "Net-(U100-VDDCORE)") (class "Default")
      (node (ref "C112") (pin "2") (pinfunction "2_2") (pintype "passive"))
      (node (ref "C113") (pin "2") (pinfunction "2_2") (pintype "passive"))
      (node (ref "U100") (pin "43") (pinfunction "VDDCORE_43") (pintype "passive"))
    )
    (net (code "53") (name "Net-(U102-EN)") (class "Default")
      (node (ref "R104") (pin "1") (pinfunction "1_1") (pintype "passive"))
      (node (ref "U102") (pin "1") (pinfunction "EN_1") (pintype "passive"))
    )
    (net (code "54") (name "Net-(U103-+Vin)") (class "Default")
      (node (ref "L103") (pin "2") (pinfunction "2_2") (pintype "passive"))
      (node (ref "U103") (pin "1") (pinfunction "+Vin_1") (pintype "power_in"))
    )
    (net (code "55") (name "Net-(U103-+Vout)") (class "Default")
      (node (ref "L102") (pin "1") (pinfunction "1_1") (pintype "passive"))
      (node (ref "U103") (pin "6") (pinfunction "+Vout_6") (pintype "power_in"))
    )
    (net (code "56") (name "Net-(U104-A)") (class "Default")
      (node (ref "R114") (pin "2") (pinfunction "2_2") (pintype "passive"))
      (node (ref "U104") (pin "1") (pinfunction "A_1") (pintype "passive"))
    )
    (net (code "57") (name "Net-(U104-C-Pad4)") (class "Default")
      (node (ref "U104") (pin "4") (pinfunction "C_4") (pintype "passive"))
      (node (ref "V101") (pin "1") (pinfunction "1_1") (pintype "passive"))
    )
    (net (code "58") (name "Net-(U105-RxD)") (class "Default")
      (node (ref "U105") (pin "1") (pinfunction "RxD_1") (pintype "open_collector"))
      (node (ref "U107") (pin "2") (pinfunction "C_2") (pintype "passive"))
    )
    (net (code "59") (name "Net-(U105-TxD)") (class "Default")
      (node (ref "R115") (pin "2") (pinfunction "2_2") (pintype "passive"))
      (node (ref "U105") (pin "4") (pinfunction "TxD_4") (pintype "input"))
      (node (ref "U106") (pin "4") (pinfunction "C_4") (pintype "passive"))
    )
    (net (code "60") (name "Net-(U106-A)") (class "Default")
      (node (ref "R117") (pin "2") (pinfunction "2_2") (pintype "passive"))
      (node (ref "U106") (pin "1") (pinfunction "A_1") (pintype "passive"))
    )
    (net (code "61") (name "Net-(U107-A)") (class "Default")
      (node (ref "R118") (pin "2") (pinfunction "2_2") (pintype "passive"))
      (node (ref "U107") (pin "1") (pinfunction "A_1") (pintype "passive"))
    )
    (net (code "62") (name "Net-(U108-A)") (class "Default")
      (node (ref "R122") (pin "2") (pinfunction "2_2") (pintype "passive"))
      (node (ref "U108") (pin "1") (pinfunction "A_1") (pintype "passive"))
    )
    (net (code "63") (name "Net-(U108-C-Pad4)") (class "Default")
      (node (ref "U108") (pin "4") (pinfunction "C_4") (pintype "passive"))
      (node (ref "V102") (pin "1") (pinfunction "1_1") (pintype "passive"))
    )
    (net (code "64") (name "Net-(U109-RxD)") (class "Default")
      (node (ref "U109") (pin "1") (pinfunction "RxD_1") (pintype "open_collector"))
      (node (ref "U111") (pin "2") (pinfunction "C_2") (pintype "passive"))
    )
    (net (code "65") (name "Net-(U109-TxD)") (class "Default")
      (node (ref "R124") (pin "1") (pinfunction "1_1") (pintype "passive"))
      (node (ref "U109") (pin "4") (pinfunction "TxD_4") (pintype "input"))
      (node (ref "U110") (pin "4") (pinfunction "C_4") (pintype "passive"))
    )
    (net (code "66") (name "Net-(U110-A)") (class "Default")
      (node (ref "R126") (pin "2") (pinfunction "2_2") (pintype "passive"))
      (node (ref "U110") (pin "1") (pinfunction "A_1") (pintype "passive"))
    )
    (net (code "67") (name "Net-(U111-A)") (class "Default")
      (node (ref "R127") (pin "1") (pinfunction "1_1") (pintype "passive"))
      (node (ref "U111") (pin "1") (pinfunction "A_1") (pintype "passive"))
    )
    (net (code "68") (name "Net-(X100-Shield)") (class "Default")
      (node (ref "R101") (pin "2") (pinfunction "2_2") (pintype "passive"))
      (node (ref "X100") (pin "Shell") (pinfunction "Shield_Shell") (pintype "passive"))
    )
    (net (code "69") (name "unconnected-(U100-PA03{slash}AIN0_1{slash}VREFA-Pad4)") (class "Default")
      (node (ref "U100") (pin "4") (pinfunction "PA03/AIN0_1/VREFA_4") (pintype "bidirectional+no_connect"))
    )
    (net (code "70") (name "unconnected-(U100-PA04{slash}AIN0_4{slash}VREFB{slash}COM0_0-Pad9)") (class "Default")
      (node (ref "U100") (pin "9") (pinfunction "PA04/AIN0_4/VREFB/COM0_0_9") (pintype "bidirectional+no_connect"))
    )
    (net (code "71") (name "unconnected-(U100-PA05{slash}AIN0_5{slash}COM0_1-Pad10)") (class "Default")
      (node (ref "U100") (pin "10") (pinfunction "PA05/AIN0_5/COM0_1_10") (pintype "bidirectional+no_connect"))
    )
    (net (code "72") (name "unconnected-(U100-PA16{slash}COM1_0{slash}COM3_0-Pad25)") (class "Default")
      (node (ref "U100") (pin "25") (pinfunction "PA16/COM1_0/COM3_0_25") (pintype "bidirectional+no_connect"))
    )
    (net (code "73") (name "unconnected-(U100-PA17{slash}COM1_1{slash}COM3_1-Pad26)") (class "Default")
      (node (ref "U100") (pin "26") (pinfunction "PA17/COM1_1/COM3_1_26") (pintype "bidirectional+no_connect"))
    )
    (net (code "74") (name "unconnected-(U100-PA22{slash}COM3_0{slash}COM5_0-Pad31)") (class "Default")
      (node (ref "U100") (pin "31") (pinfunction "PA22/COM3_0/COM5_0_31") (pintype "bidirectional+no_connect"))
    )
    (net (code "75") (name "unconnected-(U100-PA23{slash}COM3_1{slash}COM5_1-Pad32)") (class "Default")
      (node (ref "U100") (pin "32") (pinfunction "PA23/COM3_1/COM5_1_32") (pintype "bidirectional+no_connect"))
    )
    (net (code "76") (name "unconnected-(U100-PB09{slash}AIN0_3{slash}COM4_1-Pad8)") (class "Default")
      (node (ref "U100") (pin "8") (pinfunction "PB09/AIN0_3/COM4_1_8") (pintype "bidirectional+no_connect"))
    )
    (net (code "77") (name "unconnected-(U100-PB10{slash}COM4_2-Pad19)") (class "Default")
      (node (ref "U100") (pin "19") (pinfunction "PB10/COM4_2_19") (pintype "bidirectional+no_connect"))
    )
    (net (code "78") (name "unconnected-(U100-PB11{slash}COM4_3-Pad20)") (class "Default")
      (node (ref "U100") (pin "20") (pinfunction "PB11/COM4_3_20") (pintype "bidirectional+no_connect"))
    )
    (net (code "79") (name "unconnected-(U100-PB22{slash}COM5_2-Pad37)") (class "Default")
      (node (ref "U100") (pin "37") (pinfunction "PB22/COM5_2_37") (pintype "bidirectional"))
    )
    (net (code "80") (name "unconnected-(U105-NC-Pad3)") (class "Default")
      (node (ref "U105") (pin "3") (pinfunction "NC_3") (pintype "passive+no_connect"))
    )
    (net (code "81") (name "unconnected-(U105-NC-Pad8)") (class "Default")
      (node (ref "U105") (pin "8") (pinfunction "NC_8") (pintype "passive+no_connect"))
    )
    (net (code "82") (name "unconnected-(U109-NC-Pad3)") (class "Default")
      (node (ref "U109") (pin "3") (pinfunction "NC_3") (pintype "passive+no_connect"))
    )
    (net (code "83") (name "unconnected-(U109-NC-Pad8)") (class "Default")
      (node (ref "U109") (pin "8") (pinfunction "NC_8") (pintype "passive+no_connect"))
    )
    (net (code "84") (name "unconnected-(X102-Pad1)") (class "Default")
      (node (ref "X102") (pin "1") (pinfunction "1_1") (pintype "passive"))
    )
    (net (code "85") (name "unconnected-(X102-Pad2)") (class "Default")
      (node (ref "X102") (pin "2") (pinfunction "2_2") (pintype "passive"))
    )
    (net (code "86") (name "unconnected-(X102-Pad4)") (class "Default")
      (node (ref "X102") (pin "4") (pinfunction "4_4") (pintype "passive"))
    )
    (net (code "87") (name "unconnected-(X102-Pad5)") (class "Default")
      (node (ref "X102") (pin "5") (pinfunction "5_5") (pintype "passive"))
    )
    (net (code "88") (name "unconnected-(X102-Pad6)") (class "Default")
      (node (ref "X102") (pin "6") (pinfunction "6_6") (pintype "passive"))
    )
    (net (code "89") (name "unconnected-(X102-Pad9)") (class "Default")
      (node (ref "X102") (pin "9") (pinfunction "9_9") (pintype "passive"))
    )
    (net (code "90") (name "unconnected-(X102-PadSH)") (class "Default")
      (node (ref "X102") (pin "SH") (pinfunction "SH_SH") (pintype "passive"))
    )
    (net (code "91") (name "unconnected-(X103-KEY-Pad7)") (class "Default")
      (node (ref "X103") (pin "7") (pinfunction "KEY_7") (pintype "passive"))
    )
    (net (code "92") (name "unconnected-(X103-NC{slash}TDI-Pad8)") (class "Default")
      (node (ref "X103") (pin "8") (pinfunction "NC/TDI_8") (pintype "passive"))
    )
    (net (code "93") (name "unconnected-(X103-SWO{slash}TDO-Pad6)") (class "Default")
      (node (ref "X103") (pin "6") (pinfunction "SWO/TDO_6") (pintype "passive"))
    )
  )
)
